# 6x5keyboard.net
KiCad netlist of a schematic drawn in EAGLE
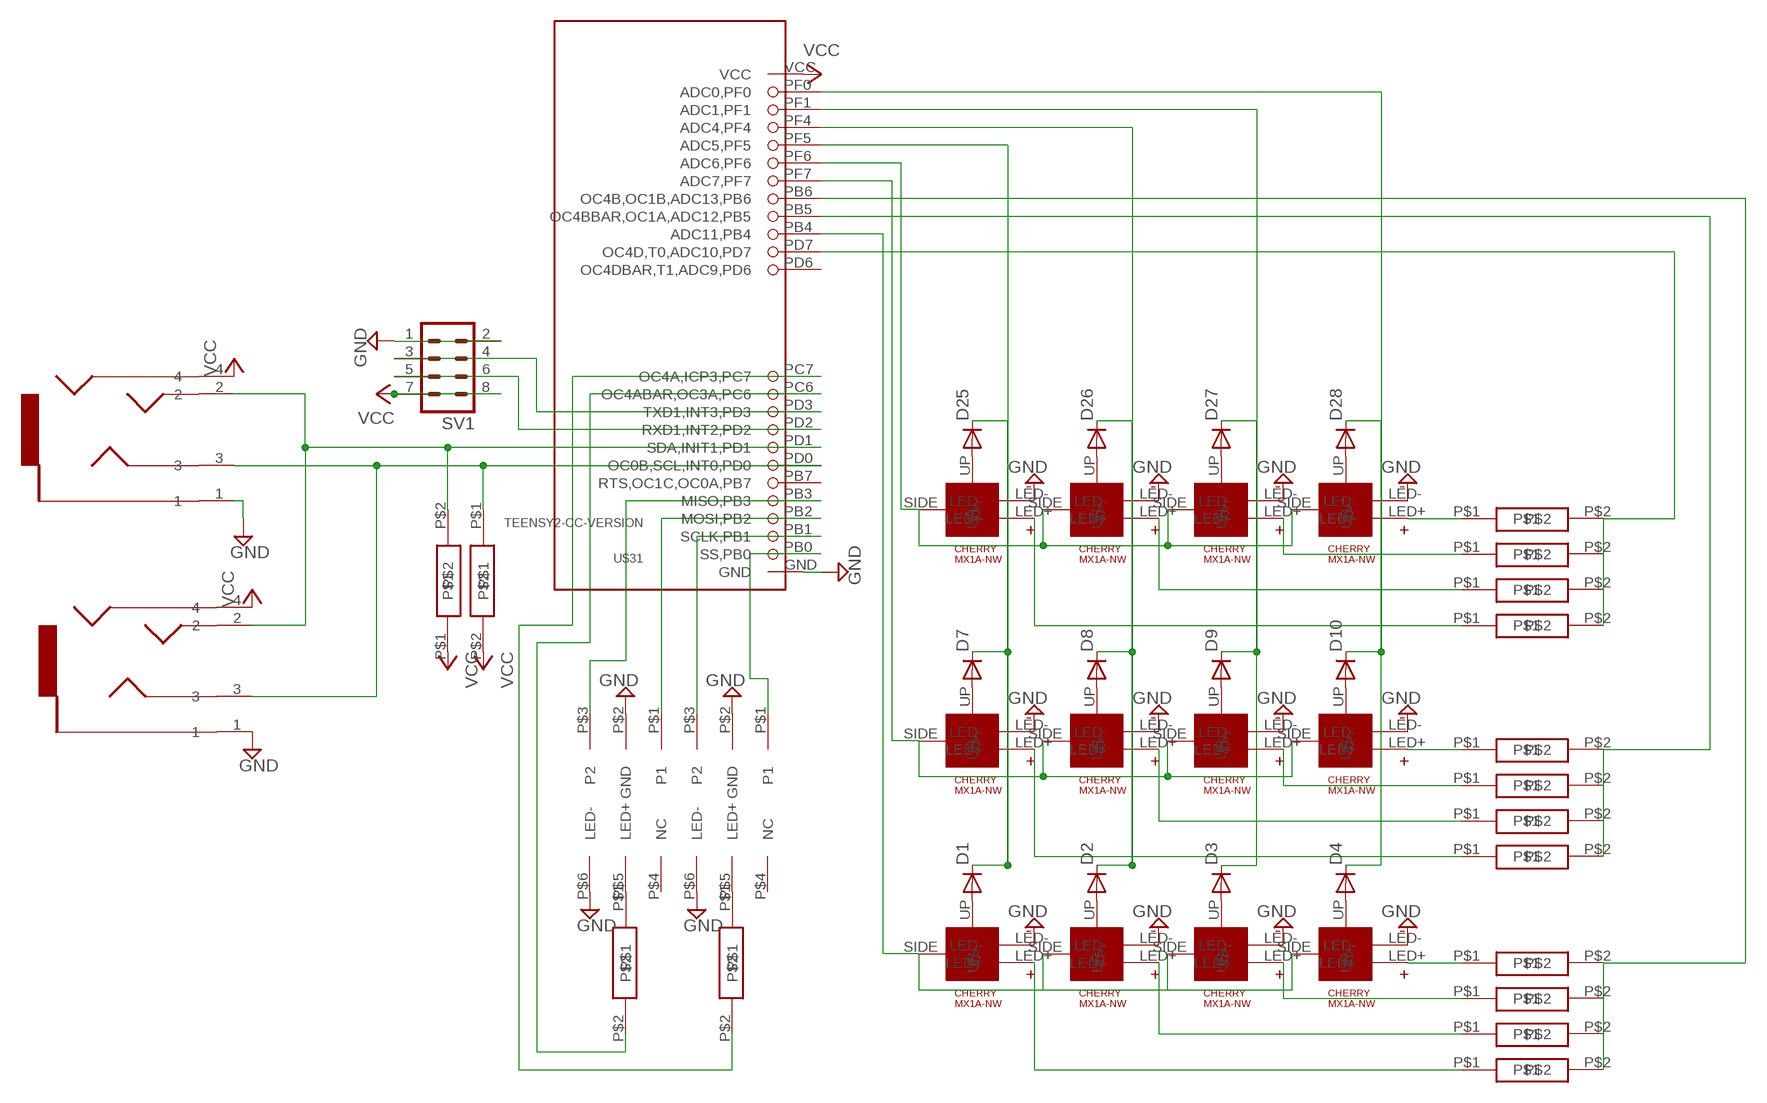
[diagram p0: schematic, sheet 1]

(export (version "E")
  (design (tool "Eeschema 10.0.6"))
  (components
    (comp (ref "COMM")
      (value "SJ-43514_HEADPHONES_3.5MM_X4")
      (footprint "eagle-import:SJ-43514_HEADPHONES-3.5MM_X4")
      (libsource (lib "eagle-import") (part "SJ-43514_HEADPHONES_3.5MM_X4"))
    )
    (comp (ref "COMM1")
      (value "SJ-43514_HEADPHONES_3.5MM_X4")
      (footprint "eagle-import:SJ-43514_HEADPHONES-3.5MM_X4")
      (libsource (lib "eagle-import") (part "SJ-43514_HEADPHONES_3.5MM_X4"))
    )
    (comp (ref "D1")
      (value "1N4148DO35-7")
      (footprint "eagle-import:DO35-7")
      (libsource (lib "eagle-import") (part "1N4148DO35-7"))
    )
    (comp (ref "D2")
      (value "1N4148DO35-7")
      (footprint "eagle-import:DO35-7")
      (libsource (lib "eagle-import") (part "1N4148DO35-7"))
    )
    (comp (ref "D3")
      (value "1N4148DO35-7")
      (footprint "eagle-import:DO35-7")
      (libsource (lib "eagle-import") (part "1N4148DO35-7"))
    )
    (comp (ref "D4")
      (value "1N4148DO35-7")
      (footprint "eagle-import:DO35-7")
      (libsource (lib "eagle-import") (part "1N4148DO35-7"))
    )
    (comp (ref "D7")
      (value "1N4148DO35-7")
      (footprint "eagle-import:DO35-7")
      (libsource (lib "eagle-import") (part "1N4148DO35-7"))
    )
    (comp (ref "D8")
      (value "1N4148DO35-7")
      (footprint "eagle-import:DO35-7")
      (libsource (lib "eagle-import") (part "1N4148DO35-7"))
    )
    (comp (ref "D9")
      (value "1N4148DO35-7")
      (footprint "eagle-import:DO35-7")
      (libsource (lib "eagle-import") (part "1N4148DO35-7"))
    )
    (comp (ref "D10")
      (value "1N4148DO35-7")
      (footprint "eagle-import:DO35-7")
      (libsource (lib "eagle-import") (part "1N4148DO35-7"))
    )
    (comp (ref "D25")
      (value "1N4148DO35-7")
      (footprint "eagle-import:DO35-7")
      (libsource (lib "eagle-import") (part "1N4148DO35-7"))
    )
    (comp (ref "D26")
      (value "1N4148DO35-7")
      (footprint "eagle-import:DO35-7")
      (libsource (lib "eagle-import") (part "1N4148DO35-7"))
    )
    (comp (ref "D27")
      (value "1N4148DO35-7")
      (footprint "eagle-import:DO35-7")
      (libsource (lib "eagle-import") (part "1N4148DO35-7"))
    )
    (comp (ref "D28")
      (value "1N4148DO35-7")
      (footprint "eagle-import:DO35-7")
      (libsource (lib "eagle-import") (part "1N4148DO35-7"))
    )
    (comp (ref "SV1")
      (value "MA04-2")
      (footprint "eagle-import:MA04-2")
      (libsource (lib "eagle-import") (part "MA04-2"))
    )
    (comp (ref "U$1")
      (value "CHERRY-MX1A-E1NW-LED")
      (footprint "eagle-import:CHERRYMX-NN-LED")
      (libsource (lib "eagle-import") (part "CHERRY-MX1A-E1NW-LED"))
    )
    (comp (ref "U$2")
      (value "CHERRY-MX1A-E1NW-LED")
      (footprint "eagle-import:CHERRYMX-NN-LED")
      (libsource (lib "eagle-import") (part "CHERRY-MX1A-E1NW-LED"))
    )
    (comp (ref "U$3")
      (value "CHERRY-MX1A-E1NW-LED")
      (footprint "eagle-import:CHERRYMX-NN-LED")
      (libsource (lib "eagle-import") (part "CHERRY-MX1A-E1NW-LED"))
    )
    (comp (ref "U$4")
      (value "CHERRY-MX1A-E1NW-LED")
      (footprint "eagle-import:CHERRYMX-NN-LED")
      (libsource (lib "eagle-import") (part "CHERRY-MX1A-E1NW-LED"))
    )
    (comp (ref "U$5")
      (value "RESISTORBIGPAD")
      (footprint "eagle-import:RESISTORBIGPAD")
      (libsource (lib "eagle-import") (part "RESISTORBIGPAD"))
    )
    (comp (ref "U$6")
      (value "RESISTORBIGPAD")
      (footprint "eagle-import:RESISTORBIGPAD")
      (libsource (lib "eagle-import") (part "RESISTORBIGPAD"))
    )
    (comp (ref "U$7")
      (value "CHERRY-MX1A-E1NW-LED")
      (footprint "eagle-import:CHERRYMX-NN-LED")
      (libsource (lib "eagle-import") (part "CHERRY-MX1A-E1NW-LED"))
    )
    (comp (ref "U$8")
      (value "CHERRY-MX1A-E1NW-LED")
      (footprint "eagle-import:CHERRYMX-NN-LED")
      (libsource (lib "eagle-import") (part "CHERRY-MX1A-E1NW-LED"))
    )
    (comp (ref "U$9")
      (value "CHERRY-MX1A-E1NW-LED")
      (footprint "eagle-import:CHERRYMX-NN-LED")
      (libsource (lib "eagle-import") (part "CHERRY-MX1A-E1NW-LED"))
    )
    (comp (ref "U$10")
      (value "CHERRY-MX1A-E1NW-LED")
      (footprint "eagle-import:CHERRYMX-NN-LED")
      (libsource (lib "eagle-import") (part "CHERRY-MX1A-E1NW-LED"))
    )
    (comp (ref "U$11")
      (value "RESISTORBIGPAD")
      (footprint "eagle-import:RESISTORBIGPAD")
      (libsource (lib "eagle-import") (part "RESISTORBIGPAD"))
    )
    (comp (ref "U$12")
      (value "RESISTORBIGPAD")
      (footprint "eagle-import:RESISTORBIGPAD")
      (libsource (lib "eagle-import") (part "RESISTORBIGPAD"))
    )
    (comp (ref "U$13")
      (value "RESISTORBIGPAD")
      (footprint "eagle-import:RESISTORBIGPAD")
      (libsource (lib "eagle-import") (part "RESISTORBIGPAD"))
    )
    (comp (ref "U$14")
      (value "RESISTORBIGPAD")
      (footprint "eagle-import:RESISTORBIGPAD")
      (libsource (lib "eagle-import") (part "RESISTORBIGPAD"))
    )
    (comp (ref "U$15")
      (value "RESISTORBIGPAD")
      (footprint "eagle-import:RESISTORBIGPAD")
      (libsource (lib "eagle-import") (part "RESISTORBIGPAD"))
    )
    (comp (ref "U$16")
      (value "RESISTORBIGPAD")
      (footprint "eagle-import:RESISTORBIGPAD")
      (libsource (lib "eagle-import") (part "RESISTORBIGPAD"))
    )
    (comp (ref "U$17")
      (value "RESISTORBIGPAD")
      (footprint "eagle-import:RESISTORBIGPAD")
      (libsource (lib "eagle-import") (part "RESISTORBIGPAD"))
    )
    (comp (ref "U$18")
      (value "RESISTORBIGPAD")
      (footprint "eagle-import:RESISTORBIGPAD")
      (libsource (lib "eagle-import") (part "RESISTORBIGPAD"))
    )
    (comp (ref "U$19")
      (value "RESISTORBIGPAD")
      (footprint "eagle-import:RESISTORBIGPAD")
      (libsource (lib "eagle-import") (part "RESISTORBIGPAD"))
    )
    (comp (ref "U$20")
      (value "RESISTORBIGPAD")
      (footprint "eagle-import:RESISTORBIGPAD")
      (libsource (lib "eagle-import") (part "RESISTORBIGPAD"))
    )
    (comp (ref "U$21")
      (value "RESISTORBIGPAD")
      (footprint "eagle-import:RESISTORBIGPAD")
      (libsource (lib "eagle-import") (part "RESISTORBIGPAD"))
    )
    (comp (ref "U$22")
      (value "RESISTORBIGPAD")
      (footprint "eagle-import:RESISTORBIGPAD")
      (libsource (lib "eagle-import") (part "RESISTORBIGPAD"))
    )
    (comp (ref "U$23")
      (value "NKK_GW_SERIES")
      (footprint "eagle-import:NKK_GW_SERIES")
      (libsource (lib "eagle-import") (part "NKK_GW_SERIES"))
    )
    (comp (ref "U$24")
      (value "NKK_GW_SERIES")
      (footprint "eagle-import:NKK_GW_SERIES")
      (libsource (lib "eagle-import") (part "NKK_GW_SERIES"))
    )
    (comp (ref "U$25")
      (value "CHERRY-MX1A-E1NW-LED")
      (footprint "eagle-import:CHERRYMX-NN-LED")
      (libsource (lib "eagle-import") (part "CHERRY-MX1A-E1NW-LED"))
    )
    (comp (ref "U$26")
      (value "CHERRY-MX1A-E1NW-LED")
      (footprint "eagle-import:CHERRYMX-NN-LED")
      (libsource (lib "eagle-import") (part "CHERRY-MX1A-E1NW-LED"))
    )
    (comp (ref "U$27")
      (value "CHERRY-MX1A-E1NW-LED")
      (footprint "eagle-import:CHERRYMX-NN-LED")
      (libsource (lib "eagle-import") (part "CHERRY-MX1A-E1NW-LED"))
    )
    (comp (ref "U$28")
      (value "CHERRY-MX1A-E1NW-LED")
      (footprint "eagle-import:CHERRYMX-NN-LED")
      (libsource (lib "eagle-import") (part "CHERRY-MX1A-E1NW-LED"))
    )
    (comp (ref "U$29")
      (value "RESISTORBIGPAD")
      (footprint "eagle-import:RESISTORBIGPAD")
      (libsource (lib "eagle-import") (part "RESISTORBIGPAD"))
    )
    (comp (ref "U$30")
      (value "RESISTORBIGPAD")
      (footprint "eagle-import:RESISTORBIGPAD")
      (libsource (lib "eagle-import") (part "RESISTORBIGPAD"))
    )
    (comp (ref "U$31")
      (value "TEENSY2-CC-VERSION")
      (footprint "eagle-import:TEENSY2")
      (libsource (lib "eagle-import") (part "TEENSY2-CC-VERSION"))
    )
  )
  (nets
    (net (code "1") (name "GND") (class "Default")
      (node (ref "COMM") (pin "1") (pinfunction "1_1") (pintype "bidirectional"))
      (node (ref "COMM1") (pin "1") (pinfunction "1_1") (pintype "bidirectional"))
      (node (ref "SV1") (pin "1") (pinfunction "1_1") (pintype "passive"))
      (node (ref "SV1") (pin "2") (pinfunction "2_2") (pintype "passive"))
      (node (ref "U$1") (pin "LED-") (pinfunction "LED-_LED-") (pintype "bidirectional"))
      (node (ref "U$10") (pin "LED-") (pinfunction "LED-_LED-") (pintype "bidirectional"))
      (node (ref "U$2") (pin "LED-") (pinfunction "LED-_LED-") (pintype "bidirectional"))
      (node (ref "U$23") (pin "P$2") (pinfunction "GND_P$2") (pintype "bidirectional"))
      (node (ref "U$23") (pin "P$6") (pinfunction "LED-_P$6") (pintype "bidirectional"))
      (node (ref "U$24") (pin "P$2") (pinfunction "GND_P$2") (pintype "bidirectional"))
      (node (ref "U$24") (pin "P$6") (pinfunction "LED-_P$6") (pintype "bidirectional"))
      (node (ref "U$25") (pin "LED-") (pinfunction "LED-_LED-") (pintype "bidirectional"))
      (node (ref "U$26") (pin "LED-") (pinfunction "LED-_LED-") (pintype "bidirectional"))
      (node (ref "U$27") (pin "LED-") (pinfunction "LED-_LED-") (pintype "bidirectional"))
      (node (ref "U$28") (pin "LED-") (pinfunction "LED-_LED-") (pintype "bidirectional"))
      (node (ref "U$3") (pin "LED-") (pinfunction "LED-_LED-") (pintype "bidirectional"))
      (node (ref "U$31") (pin "GND") (pinfunction "GND_GND") (pintype "power_in"))
      (node (ref "U$4") (pin "LED-") (pinfunction "LED-_LED-") (pintype "bidirectional"))
      (node (ref "U$7") (pin "LED-") (pinfunction "LED-_LED-") (pintype "bidirectional"))
      (node (ref "U$8") (pin "LED-") (pinfunction "LED-_LED-") (pintype "bidirectional"))
      (node (ref "U$9") (pin "LED-") (pinfunction "LED-_LED-") (pintype "bidirectional"))
    )
    (net (code "2") (name "Net-(D1-PadA)") (class "Default")
      (node (ref "D1") (pin "A") (pinfunction "A_A") (pintype "passive"))
      (node (ref "U$2") (pin "UP") (pinfunction "UP_UP") (pintype "bidirectional"))
    )
    (net (code "3") (name "Net-(D2-PadA)") (class "Default")
      (node (ref "D2") (pin "A") (pinfunction "A_A") (pintype "passive"))
      (node (ref "U$1") (pin "UP") (pinfunction "UP_UP") (pintype "bidirectional"))
    )
    (net (code "4") (name "Net-(D3-PadA)") (class "Default")
      (node (ref "D3") (pin "A") (pinfunction "A_A") (pintype "passive"))
      (node (ref "U$3") (pin "UP") (pinfunction "UP_UP") (pintype "bidirectional"))
    )
    (net (code "5") (name "Net-(D4-PadA)") (class "Default")
      (node (ref "D4") (pin "A") (pinfunction "A_A") (pintype "passive"))
      (node (ref "U$4") (pin "UP") (pinfunction "UP_UP") (pintype "bidirectional"))
    )
    (net (code "6") (name "Net-(D7-PadA)") (class "Default")
      (node (ref "D7") (pin "A") (pinfunction "A_A") (pintype "passive"))
      (node (ref "U$7") (pin "UP") (pinfunction "UP_UP") (pintype "bidirectional"))
    )
    (net (code "7") (name "Net-(D8-PadA)") (class "Default")
      (node (ref "D8") (pin "A") (pinfunction "A_A") (pintype "passive"))
      (node (ref "U$8") (pin "UP") (pinfunction "UP_UP") (pintype "bidirectional"))
    )
    (net (code "8") (name "Net-(D9-PadA)") (class "Default")
      (node (ref "D9") (pin "A") (pinfunction "A_A") (pintype "passive"))
      (node (ref "U$9") (pin "UP") (pinfunction "UP_UP") (pintype "bidirectional"))
    )
    (net (code "9") (name "Net-(D10-PadA)") (class "Default")
      (node (ref "D10") (pin "A") (pinfunction "A_A") (pintype "passive"))
      (node (ref "U$10") (pin "UP") (pinfunction "UP_UP") (pintype "bidirectional"))
    )
    (net (code "10") (name "Net-(D25-PadA)") (class "Default")
      (node (ref "D25") (pin "A") (pinfunction "A_A") (pintype "passive"))
      (node (ref "U$25") (pin "UP") (pinfunction "UP_UP") (pintype "bidirectional"))
    )
    (net (code "11") (name "Net-(D26-PadA)") (class "Default")
      (node (ref "D26") (pin "A") (pinfunction "A_A") (pintype "passive"))
      (node (ref "U$26") (pin "UP") (pinfunction "UP_UP") (pintype "bidirectional"))
    )
    (net (code "12") (name "Net-(D27-PadA)") (class "Default")
      (node (ref "D27") (pin "A") (pinfunction "A_A") (pintype "passive"))
      (node (ref "U$27") (pin "UP") (pinfunction "UP_UP") (pintype "bidirectional"))
    )
    (net (code "13") (name "Net-(D28-PadA)") (class "Default")
      (node (ref "D28") (pin "A") (pinfunction "A_A") (pintype "passive"))
      (node (ref "U$28") (pin "UP") (pinfunction "UP_UP") (pintype "bidirectional"))
    )
    (net (code "14") (name "Net-(U$1-A)") (class "Default")
      (node (ref "U$1") (pin "SIDE") (pinfunction "A_SIDE") (pintype "bidirectional"))
      (node (ref "U$2") (pin "SIDE") (pinfunction "A_SIDE") (pintype "bidirectional"))
      (node (ref "U$3") (pin "SIDE") (pinfunction "A_SIDE") (pintype "bidirectional"))
      (node (ref "U$31") (pin "PB4") (pinfunction "ADC11,PB4_PB4") (pintype "bidirectional"))
      (node (ref "U$4") (pin "SIDE") (pinfunction "A_SIDE") (pintype "bidirectional"))
    )
    (net (code "15") (name "Net-(U$1-PadLED+)") (class "Default")
      (node (ref "U$1") (pin "LED+") (pinfunction "LED+_LED+") (pintype "bidirectional"))
      (node (ref "U$6") (pin "P$1") (pinfunction "P$1_P$1") (pintype "bidirectional"))
    )
    (net (code "16") (name "Net-(U$2-PadLED+)") (class "Default")
      (node (ref "U$2") (pin "LED+") (pinfunction "LED+_LED+") (pintype "bidirectional"))
      (node (ref "U$5") (pin "P$1") (pinfunction "P$1_P$1") (pintype "bidirectional"))
    )
    (net (code "17") (name "Net-(U$10-A)") (class "Default")
      (node (ref "U$10") (pin "SIDE") (pinfunction "A_SIDE") (pintype "bidirectional"))
      (node (ref "U$31") (pin "PF7") (pinfunction "ADC7,PF7_PF7") (pintype "bidirectional"))
      (node (ref "U$7") (pin "SIDE") (pinfunction "A_SIDE") (pintype "bidirectional"))
      (node (ref "U$8") (pin "SIDE") (pinfunction "A_SIDE") (pintype "bidirectional"))
      (node (ref "U$9") (pin "SIDE") (pinfunction "A_SIDE") (pintype "bidirectional"))
    )
    (net (code "18") (name "Net-(U$10-PadLED+)") (class "Default")
      (node (ref "U$10") (pin "LED+") (pinfunction "LED+_LED+") (pintype "bidirectional"))
      (node (ref "U$13") (pin "P$1") (pinfunction "P$1_P$1") (pintype "bidirectional"))
    )
    (net (code "19") (name "Net-(U$11-PadP$1)") (class "Default")
      (node (ref "U$11") (pin "P$1") (pinfunction "P$1_P$1") (pintype "bidirectional"))
      (node (ref "U$3") (pin "LED+") (pinfunction "LED+_LED+") (pintype "bidirectional"))
    )
    (net (code "20") (name "Net-(U$12-PadP$1)") (class "Default")
      (node (ref "U$12") (pin "P$1") (pinfunction "P$1_P$1") (pintype "bidirectional"))
      (node (ref "U$4") (pin "LED+") (pinfunction "LED+_LED+") (pintype "bidirectional"))
    )
    (net (code "21") (name "Net-(U$14-PadP$1)") (class "Default")
      (node (ref "U$14") (pin "P$1") (pinfunction "P$1_P$1") (pintype "bidirectional"))
      (node (ref "U$9") (pin "LED+") (pinfunction "LED+_LED+") (pintype "bidirectional"))
    )
    (net (code "22") (name "Net-(U$15-PadP$1)") (class "Default")
      (node (ref "U$15") (pin "P$1") (pinfunction "P$1_P$1") (pintype "bidirectional"))
      (node (ref "U$8") (pin "LED+") (pinfunction "LED+_LED+") (pintype "bidirectional"))
    )
    (net (code "23") (name "Net-(U$16-PadP$1)") (class "Default")
      (node (ref "U$16") (pin "P$1") (pinfunction "P$1_P$1") (pintype "bidirectional"))
      (node (ref "U$7") (pin "LED+") (pinfunction "LED+_LED+") (pintype "bidirectional"))
    )
    (net (code "24") (name "Net-(U$17-PadP$1)") (class "Default")
      (node (ref "U$17") (pin "P$1") (pinfunction "P$1_P$1") (pintype "bidirectional"))
      (node (ref "U$28") (pin "LED+") (pinfunction "LED+_LED+") (pintype "bidirectional"))
    )
    (net (code "25") (name "Net-(U$18-PadP$1)") (class "Default")
      (node (ref "U$18") (pin "P$1") (pinfunction "P$1_P$1") (pintype "bidirectional"))
      (node (ref "U$27") (pin "LED+") (pinfunction "LED+_LED+") (pintype "bidirectional"))
    )
    (net (code "26") (name "Net-(U$19-PadP$1)") (class "Default")
      (node (ref "U$19") (pin "P$1") (pinfunction "P$1_P$1") (pintype "bidirectional"))
      (node (ref "U$26") (pin "LED+") (pinfunction "LED+_LED+") (pintype "bidirectional"))
    )
    (net (code "27") (name "Net-(U$20-PadP$1)") (class "Default")
      (node (ref "U$20") (pin "P$1") (pinfunction "P$1_P$1") (pintype "bidirectional"))
      (node (ref "U$25") (pin "LED+") (pinfunction "LED+_LED+") (pintype "bidirectional"))
    )
    (net (code "28") (name "Net-(U$23-LED+)") (class "Default")
      (node (ref "U$23") (pin "P$5") (pinfunction "LED+_P$5") (pintype "bidirectional"))
      (node (ref "U$29") (pin "P$1") (pinfunction "P$1_P$1") (pintype "bidirectional"))
    )
    (net (code "29") (name "Net-(U$23-P1)") (class "Default")
      (node (ref "U$23") (pin "P$1") (pinfunction "P1_P$1") (pintype "bidirectional"))
      (node (ref "U$31") (pin "PB2") (pinfunction "MOSI,PB2_PB2") (pintype "bidirectional"))
    )
    (net (code "30") (name "Net-(U$23-P2)") (class "Default")
      (node (ref "U$23") (pin "P$3") (pinfunction "P2_P$3") (pintype "bidirectional"))
      (node (ref "U$31") (pin "PB3") (pinfunction "MISO,PB3_PB3") (pintype "bidirectional"))
    )
    (net (code "31") (name "Net-(U$24-LED+)") (class "Default")
      (node (ref "U$24") (pin "P$5") (pinfunction "LED+_P$5") (pintype "bidirectional"))
      (node (ref "U$30") (pin "P$1") (pinfunction "P$1_P$1") (pintype "bidirectional"))
    )
    (net (code "32") (name "Net-(U$24-P1)") (class "Default")
      (node (ref "U$24") (pin "P$1") (pinfunction "P1_P$1") (pintype "bidirectional"))
      (node (ref "U$31") (pin "PB0") (pinfunction "SS,PB0_PB0") (pintype "bidirectional"))
    )
    (net (code "33") (name "Net-(U$24-P2)") (class "Default")
      (node (ref "U$24") (pin "P$3") (pinfunction "P2_P$3") (pintype "bidirectional"))
      (node (ref "U$31") (pin "PB1") (pinfunction "SCLK,PB1_PB1") (pintype "bidirectional"))
    )
    (net (code "34") (name "Net-(U$25-A)") (class "Default")
      (node (ref "U$25") (pin "SIDE") (pinfunction "A_SIDE") (pintype "bidirectional"))
      (node (ref "U$26") (pin "SIDE") (pinfunction "A_SIDE") (pintype "bidirectional"))
      (node (ref "U$27") (pin "SIDE") (pinfunction "A_SIDE") (pintype "bidirectional"))
      (node (ref "U$28") (pin "SIDE") (pinfunction "A_SIDE") (pintype "bidirectional"))
      (node (ref "U$31") (pin "PF6") (pinfunction "ADC6,PF6_PF6") (pintype "bidirectional"))
    )
    (net (code "35") (name "Net-(U$31-ADC0,PF0)") (class "Default")
      (node (ref "D10") (pin "C") (pinfunction "C_C") (pintype "passive"))
      (node (ref "D28") (pin "C") (pinfunction "C_C") (pintype "passive"))
      (node (ref "D4") (pin "C") (pinfunction "C_C") (pintype "passive"))
      (node (ref "U$31") (pin "PF0") (pinfunction "ADC0,PF0_PF0") (pintype "bidirectional"))
    )
    (net (code "36") (name "Net-(U$31-ADC1,PF1)") (class "Default")
      (node (ref "D27") (pin "C") (pinfunction "C_C") (pintype "passive"))
      (node (ref "D3") (pin "C") (pinfunction "C_C") (pintype "passive"))
      (node (ref "D9") (pin "C") (pinfunction "C_C") (pintype "passive"))
      (node (ref "U$31") (pin "PF1") (pinfunction "ADC1,PF1_PF1") (pintype "bidirectional"))
    )
    (net (code "37") (name "Net-(U$31-ADC4,PF4)") (class "Default")
      (node (ref "D2") (pin "C") (pinfunction "C_C") (pintype "passive"))
      (node (ref "D26") (pin "C") (pinfunction "C_C") (pintype "passive"))
      (node (ref "D8") (pin "C") (pinfunction "C_C") (pintype "passive"))
      (node (ref "U$31") (pin "PF4") (pinfunction "ADC4,PF4_PF4") (pintype "bidirectional"))
    )
    (net (code "38") (name "Net-(U$31-ADC5,PF5)") (class "Default")
      (node (ref "D1") (pin "C") (pinfunction "C_C") (pintype "passive"))
      (node (ref "D25") (pin "C") (pinfunction "C_C") (pintype "passive"))
      (node (ref "D7") (pin "C") (pinfunction "C_C") (pintype "passive"))
      (node (ref "U$31") (pin "PF5") (pinfunction "ADC5,PF5_PF5") (pintype "bidirectional"))
    )
    (net (code "39") (name "Net-(U$31-OC0B,SCL,INT0,PD0)") (class "Default")
      (node (ref "COMM") (pin "3") (pinfunction "3_3") (pintype "bidirectional"))
      (node (ref "COMM1") (pin "3") (pinfunction "3_3") (pintype "bidirectional"))
      (node (ref "U$22") (pin "P$1") (pinfunction "P$1_P$1") (pintype "bidirectional"))
      (node (ref "U$31") (pin "PD0") (pinfunction "OC0B,SCL,INT0,PD0_PD0") (pintype "bidirectional"))
    )
    (net (code "40") (name "Net-(U$31-OC4A,ICP3,PC7)") (class "Default")
      (node (ref "U$30") (pin "P$2") (pinfunction "P$2_P$2") (pintype "bidirectional"))
      (node (ref "U$31") (pin "PC7") (pinfunction "OC4A,ICP3,PC7_PC7") (pintype "bidirectional"))
    )
    (net (code "41") (name "Net-(U$31-OC4ABAR,OC3A,PC6)") (class "Default")
      (node (ref "U$29") (pin "P$2") (pinfunction "P$2_P$2") (pintype "bidirectional"))
      (node (ref "U$31") (pin "PC6") (pinfunction "OC4ABAR,OC3A,PC6_PC6") (pintype "bidirectional"))
    )
    (net (code "42") (name "Net-(U$31-OC4B,OC1B,ADC13,PB6)") (class "Default")
      (node (ref "U$11") (pin "P$2") (pinfunction "P$2_P$2") (pintype "bidirectional"))
      (node (ref "U$12") (pin "P$2") (pinfunction "P$2_P$2") (pintype "bidirectional"))
      (node (ref "U$31") (pin "PB6") (pinfunction "OC4B,OC1B,ADC13,PB6_PB6") (pintype "bidirectional"))
      (node (ref "U$5") (pin "P$2") (pinfunction "P$2_P$2") (pintype "bidirectional"))
      (node (ref "U$6") (pin "P$2") (pinfunction "P$2_P$2") (pintype "bidirectional"))
    )
    (net (code "43") (name "Net-(U$31-OC4BBAR,OC1A,ADC12,PB5)") (class "Default")
      (node (ref "U$13") (pin "P$2") (pinfunction "P$2_P$2") (pintype "bidirectional"))
      (node (ref "U$14") (pin "P$2") (pinfunction "P$2_P$2") (pintype "bidirectional"))
      (node (ref "U$15") (pin "P$2") (pinfunction "P$2_P$2") (pintype "bidirectional"))
      (node (ref "U$16") (pin "P$2") (pinfunction "P$2_P$2") (pintype "bidirectional"))
      (node (ref "U$31") (pin "PB5") (pinfunction "OC4BBAR,OC1A,ADC12,PB5_PB5") (pintype "bidirectional"))
    )
    (net (code "44") (name "Net-(U$31-OC4D,T0,ADC10,PD7)") (class "Default")
      (node (ref "U$17") (pin "P$2") (pinfunction "P$2_P$2") (pintype "bidirectional"))
      (node (ref "U$18") (pin "P$2") (pinfunction "P$2_P$2") (pintype "bidirectional"))
      (node (ref "U$19") (pin "P$2") (pinfunction "P$2_P$2") (pintype "bidirectional"))
      (node (ref "U$20") (pin "P$2") (pinfunction "P$2_P$2") (pintype "bidirectional"))
      (node (ref "U$31") (pin "PD7") (pinfunction "OC4D,T0,ADC10,PD7_PD7") (pintype "bidirectional"))
    )
    (net (code "45") (name "Net-(U$31-RXD1,INT2,PD2)") (class "Default")
      (node (ref "SV1") (pin "5") (pinfunction "5_5") (pintype "passive"))
      (node (ref "SV1") (pin "6") (pinfunction "6_6") (pintype "passive"))
      (node (ref "U$31") (pin "PD2") (pinfunction "RXD1,INT2,PD2_PD2") (pintype "bidirectional"))
    )
    (net (code "46") (name "Net-(U$31-SDA,INIT1,PD1)") (class "Default")
      (node (ref "COMM") (pin "2") (pinfunction "2_2") (pintype "bidirectional"))
      (node (ref "COMM1") (pin "2") (pinfunction "2_2") (pintype "bidirectional"))
      (node (ref "U$21") (pin "P$2") (pinfunction "P$2_P$2") (pintype "bidirectional"))
      (node (ref "U$31") (pin "PD1") (pinfunction "SDA,INIT1,PD1_PD1") (pintype "bidirectional"))
    )
    (net (code "47") (name "Net-(U$31-TXD1,INT3,PD3)") (class "Default")
      (node (ref "SV1") (pin "3") (pinfunction "3_3") (pintype "passive"))
      (node (ref "SV1") (pin "4") (pinfunction "4_4") (pintype "passive"))
      (node (ref "U$31") (pin "PD3") (pinfunction "TXD1,INT3,PD3_PD3") (pintype "bidirectional"))
    )
    (net (code "48") (name "VCC") (class "Default")
      (node (ref "COMM") (pin "4") (pinfunction "4_4") (pintype "bidirectional"))
      (node (ref "COMM1") (pin "4") (pinfunction "4_4") (pintype "bidirectional"))
      (node (ref "SV1") (pin "7") (pinfunction "7_7") (pintype "passive"))
      (node (ref "SV1") (pin "8") (pinfunction "8_8") (pintype "passive"))
      (node (ref "U$21") (pin "P$1") (pinfunction "P$1_P$1") (pintype "bidirectional"))
      (node (ref "U$22") (pin "P$2") (pinfunction "P$2_P$2") (pintype "bidirectional"))
      (node (ref "U$31") (pin "VCC") (pinfunction "VCC_VCC") (pintype "power_in"))
    )
    (net (code "49") (name "unconnected-(U$23-NC-PadP$4)") (class "Default")
      (node (ref "U$23") (pin "P$4") (pinfunction "NC_P$4") (pintype "bidirectional"))
    )
    (net (code "50") (name "unconnected-(U$24-NC-PadP$4)") (class "Default")
      (node (ref "U$24") (pin "P$4") (pinfunction "NC_P$4") (pintype "bidirectional"))
    )
    (net (code "51") (name "unconnected-(U$31-OC4DBAR,T1,ADC9,PD6-PadPD6)") (class "Default")
      (node (ref "U$31") (pin "PD6") (pinfunction "OC4DBAR,T1,ADC9,PD6_PD6") (pintype "bidirectional"))
    )
    (net (code "52") (name "unconnected-(U$31-RTS,OC1C,OC0A,PB7-PadPB7)") (class "Default")
      (node (ref "U$31") (pin "PB7") (pinfunction "RTS,OC1C,OC0A,PB7_PB7") (pintype "bidirectional"))
    )
  )
)
